# Top.net
KiCad netlist of a schematic drawn in Altium Designer
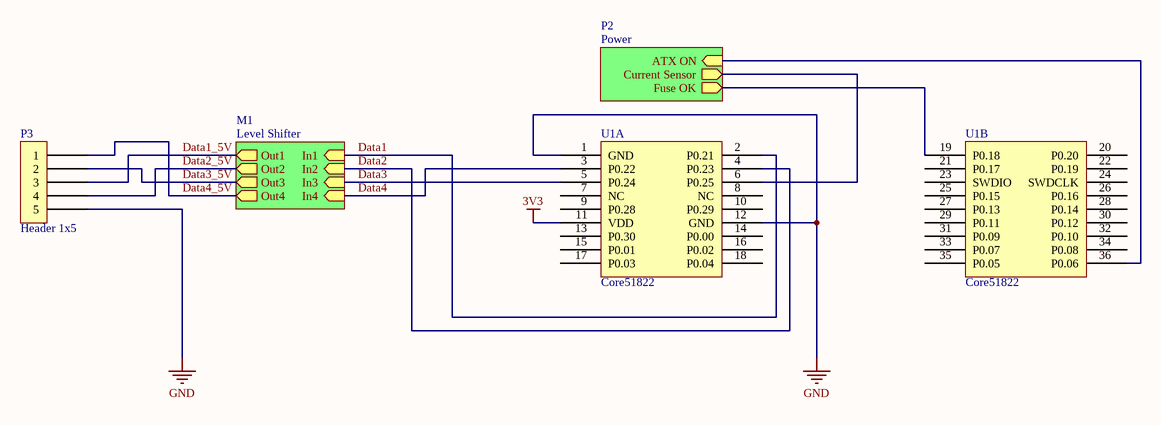
[diagram p0: Top.SchDoc]

(export (version "E")
  (design (tool "Eeschema 10.0.6"))
  (components
    (comp (ref "P3")
      (value "Header 1x5")
      (footprint "Header 1x5 male")
      (libsource (lib "Headers") (part "Header 1x5"))
    )
    (comp (ref "U1")
      (value "Core51822")
      (footprint "Core51822")
      (libsource (lib "Modules") (part "Core51822"))
    )
  )
  (nets
    (net (code "1") (name "/ATX ON") (class "Default")
      (node (ref "U1") (pin "36") (pinfunction "P0.06_36") (pintype "passive"))
    )
    (net (code "2") (name "/Current Sensor") (class "Default")
      (node (ref "U1") (pin "6") (pinfunction "P0.25_6") (pintype "passive"))
    )
    (net (code "3") (name "/Data1") (class "Default")
      (node (ref "U1") (pin "2") (pinfunction "P0.21_2") (pintype "passive"))
    )
    (net (code "4") (name "/Data1_5V") (class "Default")
      (node (ref "P3") (pin "3") (pinfunction "3_3") (pintype "passive"))
    )
    (net (code "5") (name "/Data2") (class "Default")
      (node (ref "U1") (pin "4") (pinfunction "P0.23_4") (pintype "passive"))
    )
    (net (code "6") (name "/Data2_5V") (class "Default")
      (node (ref "P3") (pin "4") (pinfunction "4_4") (pintype "passive"))
    )
    (net (code "7") (name "/Data3") (class "Default")
      (node (ref "U1") (pin "5") (pinfunction "P0.24_5") (pintype "passive"))
    )
    (net (code "8") (name "/Data3_5V") (class "Default")
      (node (ref "P3") (pin "2") (pinfunction "2_2") (pintype "passive"))
    )
    (net (code "9") (name "/Data4") (class "Default")
      (node (ref "U1") (pin "3") (pinfunction "P0.22_3") (pintype "passive"))
    )
    (net (code "10") (name "/Data4_5V") (class "Default")
      (node (ref "P3") (pin "1") (pinfunction "1_1") (pintype "passive"))
    )
    (net (code "11") (name "/Fuse OK") (class "Default")
      (node (ref "U1") (pin "19") (pinfunction "P0.18_19") (pintype "passive"))
    )
    (net (code "12") (name "3V3") (class "Default")
      (node (ref "U1") (pin "11") (pinfunction "VDD_11") (pintype "passive"))
    )
    (net (code "13") (name "GND") (class "Default")
      (node (ref "P3") (pin "5") (pinfunction "5_5") (pintype "passive"))
      (node (ref "U1") (pin "1") (pinfunction "GND_1") (pintype "passive"))
      (node (ref "U1") (pin "12") (pinfunction "GND_12") (pintype "passive"))
    )
    (net (code "14") (name "unconnected-(U1A-NC-Pad7)") (class "Default")
      (node (ref "U1") (pin "7") (pinfunction "NC_7") (pintype "passive"))
    )
    (net (code "15") (name "unconnected-(U1A-NC-Pad8)") (class "Default")
      (node (ref "U1") (pin "8") (pinfunction "NC_8") (pintype "passive"))
    )
    (net (code "16") (name "unconnected-(U1A-P0.00-Pad14)") (class "Default")
      (node (ref "U1") (pin "14") (pinfunction "P0.00_14") (pintype "passive"))
    )
    (net (code "17") (name "unconnected-(U1A-P0.01-Pad15)") (class "Default")
      (node (ref "U1") (pin "15") (pinfunction "P0.01_15") (pintype "passive"))
    )
    (net (code "18") (name "unconnected-(U1A-P0.02-Pad16)") (class "Default")
      (node (ref "U1") (pin "16") (pinfunction "P0.02_16") (pintype "passive"))
    )
    (net (code "19") (name "unconnected-(U1A-P0.03-Pad17)") (class "Default")
      (node (ref "U1") (pin "17") (pinfunction "P0.03_17") (pintype "passive"))
    )
    (net (code "20") (name "unconnected-(U1A-P0.04-Pad18)") (class "Default")
      (node (ref "U1") (pin "18") (pinfunction "P0.04_18") (pintype "passive"))
    )
    (net (code "21") (name "unconnected-(U1A-P0.28-Pad9)") (class "Default")
      (node (ref "U1") (pin "9") (pinfunction "P0.28_9") (pintype "passive"))
    )
    (net (code "22") (name "unconnected-(U1A-P0.29-Pad10)") (class "Default")
      (node (ref "U1") (pin "10") (pinfunction "P0.29_10") (pintype "passive"))
    )
    (net (code "23") (name "unconnected-(U1A-P0.30-Pad13)") (class "Default")
      (node (ref "U1") (pin "13") (pinfunction "P0.30_13") (pintype "passive"))
    )
    (net (code "24") (name "unconnected-(U1B-P0.05-Pad35)") (class "Default")
      (node (ref "U1") (pin "35") (pinfunction "P0.05_35") (pintype "passive"))
    )
    (net (code "25") (name "unconnected-(U1B-P0.07-Pad33)") (class "Default")
      (node (ref "U1") (pin "33") (pinfunction "P0.07_33") (pintype "passive"))
    )
    (net (code "26") (name "unconnected-(U1B-P0.08-Pad34)") (class "Default")
      (node (ref "U1") (pin "34") (pinfunction "P0.08_34") (pintype "passive"))
    )
    (net (code "27") (name "unconnected-(U1B-P0.09-Pad31)") (class "Default")
      (node (ref "U1") (pin "31") (pinfunction "P0.09_31") (pintype "passive"))
    )
    (net (code "28") (name "unconnected-(U1B-P0.10-Pad32)") (class "Default")
      (node (ref "U1") (pin "32") (pinfunction "P0.10_32") (pintype "passive"))
    )
    (net (code "29") (name "unconnected-(U1B-P0.11-Pad29)") (class "Default")
      (node (ref "U1") (pin "29") (pinfunction "P0.11_29") (pintype "passive"))
    )
    (net (code "30") (name "unconnected-(U1B-P0.12-Pad30)") (class "Default")
      (node (ref "U1") (pin "30") (pinfunction "P0.12_30") (pintype "passive"))
    )
    (net (code "31") (name "unconnected-(U1B-P0.13-Pad27)") (class "Default")
      (node (ref "U1") (pin "27") (pinfunction "P0.13_27") (pintype "passive"))
    )
    (net (code "32") (name "unconnected-(U1B-P0.14-Pad28)") (class "Default")
      (node (ref "U1") (pin "28") (pinfunction "P0.14_28") (pintype "passive"))
    )
    (net (code "33") (name "unconnected-(U1B-P0.15-Pad25)") (class "Default")
      (node (ref "U1") (pin "25") (pinfunction "P0.15_25") (pintype "passive"))
    )
    (net (code "34") (name "unconnected-(U1B-P0.16-Pad26)") (class "Default")
      (node (ref "U1") (pin "26") (pinfunction "P0.16_26") (pintype "passive"))
    )
    (net (code "35") (name "unconnected-(U1B-P0.17-Pad21)") (class "Default")
      (node (ref "U1") (pin "21") (pinfunction "P0.17_21") (pintype "power_in"))
    )
    (net (code "36") (name "unconnected-(U1B-P0.19-Pad22)") (class "Default")
      (node (ref "U1") (pin "22") (pinfunction "P0.19_22") (pintype "passive"))
    )
    (net (code "37") (name "unconnected-(U1B-P0.20-Pad20)") (class "Default")
      (node (ref "U1") (pin "20") (pinfunction "P0.20_20") (pintype "passive"))
    )
    (net (code "38") (name "unconnected-(U1B-SWDCLK-Pad24)") (class "Default")
      (node (ref "U1") (pin "24") (pinfunction "SWDCLK_24") (pintype "passive"))
    )
    (net (code "39") (name "unconnected-(U1B-SWDIO-Pad23)") (class "Default")
      (node (ref "U1") (pin "23") (pinfunction "SWDIO_23") (pintype "passive"))
    )
  )
)
